# dcc.net
KiCad netlist of a schematic drawn in EAGLE
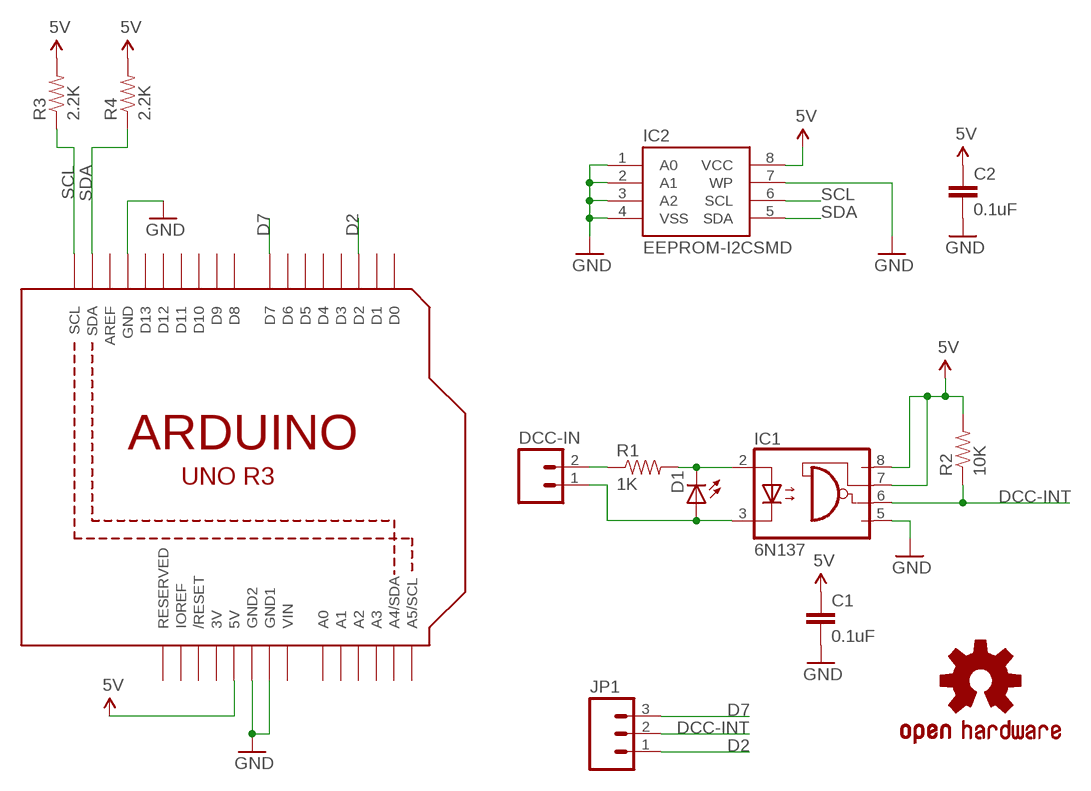
[diagram p0: schematic, sheet 1]

(export (version "E")
  (design (tool "Eeschema 10.0.6"))
  (components
    (comp (ref "C1")
      (value "0.1uF")
      (footprint "eagle-import:CAP-PTH-SMALL")
      (libsource (lib "eagle-import") (part "CAPPTH"))
    )
    (comp (ref "C2")
      (value "0.1uF")
      (footprint "eagle-import:0603-CAP")
      (libsource (lib "eagle-import") (part "0.1UF-25V(+80/-20%)(0603)"))
    )
    (comp (ref "D1")
      (value "LED5MM")
      (footprint "eagle-import:LED5MM")
      (libsource (lib "eagle-import") (part "LED5MM"))
    )
    (comp (ref "DCC-IN")
      (value "M025MM")
      (footprint "eagle-import:SCREWTERMINAL-5MM-2")
      (libsource (lib "eagle-import") (part "M025MM"))
    )
    (comp (ref "IC1")
      (value "6N137")
      (footprint "eagle-import:DIL08")
      (libsource (lib "eagle-import") (part "6N137"))
    )
    (comp (ref "IC2")
      (value "EEPROM-I2CSMD")
      (footprint "eagle-import:SO08")
      (libsource (lib "eagle-import") (part "EEPROM-I2CSMD"))
    )
    (comp (ref "JP1")
      (value "M03PTH")
      (footprint "eagle-import:1X03")
      (libsource (lib "eagle-import") (part "M03PTH"))
    )
    (comp (ref "LOGO1")
      (value "OSHW-LOGOL")
      (footprint "eagle-import:OSHW-LOGO-L")
      (libsource (lib "eagle-import") (part "OSHW-LOGOL"))
    )
    (comp (ref "R1")
      (value "1K")
      (footprint "eagle-import:AXIAL-0.4")
      (libsource (lib "eagle-import") (part "RESISTORPTH-1/4W"))
    )
    (comp (ref "R2")
      (value "10K")
      (footprint "eagle-import:AXIAL-0.4")
      (libsource (lib "eagle-import") (part "RESISTORPTH-1/4W"))
    )
    (comp (ref "R3")
      (value "2.2K")
      (footprint "eagle-import:0603-RES")
      (libsource (lib "eagle-import") (part "RESISTOR0603-RES"))
    )
    (comp (ref "R4")
      (value "2.2K")
      (footprint "eagle-import:0603-RES")
      (libsource (lib "eagle-import") (part "RESISTOR0603-RES"))
    )
    (comp (ref "U1")
      (value "ARDUINOR3-JUSTPINS")
      (footprint "eagle-import:ARDUINOR3")
      (libsource (lib "eagle-import") (part "ARDUINOR3-JUSTPINS"))
    )
  )
  (nets
    (net (code "1") (name "/3V") (class "Default")
      (node (ref "U1") (pin "3V") (pinfunction "3V_3V") (pintype "power_in"))
    )
    (net (code "2") (name "/D2") (class "Default")
      (node (ref "JP1") (pin "1") (pinfunction "1_1") (pintype "passive"))
      (node (ref "U1") (pin "D2") (pinfunction "D2_D2") (pintype "bidirectional"))
    )
    (net (code "3") (name "/D7") (class "Default")
      (node (ref "JP1") (pin "3") (pinfunction "3_3") (pintype "passive"))
      (node (ref "U1") (pin "D7") (pinfunction "D7_D7") (pintype "bidirectional"))
    )
    (net (code "4") (name "/DCC-INT") (class "Default")
      (node (ref "IC1") (pin "6") (pinfunction "VO_6") (pintype "passive"))
      (node (ref "JP1") (pin "2") (pinfunction "2_2") (pintype "passive"))
      (node (ref "R2") (pin "P$1") (pinfunction "1_P$1") (pintype "passive"))
    )
    (net (code "5") (name "/SCL") (class "Default")
      (node (ref "IC2") (pin "6") (pinfunction "SCL_6") (pintype "bidirectional"))
      (node (ref "R3") (pin "1") (pinfunction "1_1") (pintype "passive"))
      (node (ref "U1") (pin "SCL") (pinfunction "SCL_SCL") (pintype "bidirectional"))
    )
    (net (code "6") (name "/SDA") (class "Default")
      (node (ref "IC2") (pin "5") (pinfunction "SDA_5") (pintype "bidirectional"))
      (node (ref "R4") (pin "1") (pinfunction "1_1") (pintype "passive"))
      (node (ref "U1") (pin "SDA") (pinfunction "SDA_SDA") (pintype "bidirectional"))
    )
    (net (code "7") (name "/VIN") (class "Default")
      (node (ref "U1") (pin "VIN") (pinfunction "VIN_VIN") (pintype "power_in"))
    )
    (net (code "8") (name "5V") (class "Default")
      (node (ref "C1") (pin "1") (pinfunction "1_1") (pintype "passive"))
      (node (ref "C2") (pin "1") (pinfunction "1_1") (pintype "passive"))
      (node (ref "IC1") (pin "7") (pinfunction "VE_7") (pintype "passive"))
      (node (ref "IC1") (pin "8") (pinfunction "VCC_8") (pintype "passive"))
      (node (ref "IC2") (pin "8") (pinfunction "VCC_8") (pintype "power_in"))
      (node (ref "R2") (pin "P$2") (pinfunction "2_P$2") (pintype "passive"))
      (node (ref "R3") (pin "2") (pinfunction "2_2") (pintype "passive"))
      (node (ref "R4") (pin "2") (pinfunction "2_2") (pintype "passive"))
      (node (ref "U1") (pin "5V") (pinfunction "5V_5V") (pintype "power_in"))
    )
    (net (code "9") (name "GND") (class "Default")
      (node (ref "C1") (pin "2") (pinfunction "2_2") (pintype "passive"))
      (node (ref "C2") (pin "2") (pinfunction "2_2") (pintype "passive"))
      (node (ref "IC1") (pin "5") (pinfunction "GND_5") (pintype "passive"))
      (node (ref "IC2") (pin "1") (pinfunction "A0_1") (pintype "bidirectional"))
      (node (ref "IC2") (pin "2") (pinfunction "A1_2") (pintype "bidirectional"))
      (node (ref "IC2") (pin "3") (pinfunction "A2_3") (pintype "bidirectional"))
      (node (ref "IC2") (pin "4") (pinfunction "VSS_4") (pintype "power_in"))
      (node (ref "IC2") (pin "7") (pinfunction "WP_7") (pintype "bidirectional"))
      (node (ref "U1") (pin "GND") (pinfunction "GND_GND") (pintype "power_in"))
      (node (ref "U1") (pin "GND1") (pinfunction "GND1_GND1") (pintype "power_in"))
      (node (ref "U1") (pin "GND2") (pinfunction "GND2_GND2") (pintype "power_in"))
    )
    (net (code "10") (name "Net-(D1-C)") (class "Default")
      (node (ref "D1") (pin "K") (pinfunction "C_K") (pintype "passive"))
      (node (ref "IC1") (pin "2") (pinfunction "A_2") (pintype "passive"))
      (node (ref "R1") (pin "P$2") (pinfunction "2_P$2") (pintype "passive"))
    )
    (net (code "11") (name "Net-(IC1-C)") (class "Default")
      (node (ref "D1") (pin "A") (pinfunction "A_A") (pintype "passive"))
      (node (ref "DCC-IN") (pin "1") (pinfunction "1_1") (pintype "passive"))
      (node (ref "IC1") (pin "3") (pinfunction "C_3") (pintype "passive"))
    )
    (net (code "12") (name "Net-(R1-1)") (class "Default")
      (node (ref "DCC-IN") (pin "2") (pinfunction "2_2") (pintype "passive"))
      (node (ref "R1") (pin "P$1") (pinfunction "1_P$1") (pintype "passive"))
    )
    (net (code "13") (name "unconnected-(U1-A4{slash}SDA-PadA4)") (class "Default")
      (node (ref "U1") (pin "A4") (pinfunction "A4/SDA_A4") (pintype "bidirectional"))
    )
    (net (code "14") (name "unconnected-(U1-A5{slash}SCL-PadA5)") (class "Default")
      (node (ref "U1") (pin "A5") (pinfunction "A5/SCL_A5") (pintype "bidirectional"))
    )
    (net (code "15") (name "unconnected-(U1-PadA0)") (class "Default")
      (node (ref "U1") (pin "A0") (pinfunction "A0_A0") (pintype "bidirectional"))
    )
    (net (code "16") (name "unconnected-(U1-PadA1)") (class "Default")
      (node (ref "U1") (pin "A1") (pinfunction "A1_A1") (pintype "bidirectional"))
    )
    (net (code "17") (name "unconnected-(U1-PadA2)") (class "Default")
      (node (ref "U1") (pin "A2") (pinfunction "A2_A2") (pintype "bidirectional"))
    )
    (net (code "18") (name "unconnected-(U1-PadA3)") (class "Default")
      (node (ref "U1") (pin "A3") (pinfunction "A3_A3") (pintype "bidirectional"))
    )
    (net (code "19") (name "unconnected-(U1-PadAREF)") (class "Default")
      (node (ref "U1") (pin "AREF") (pinfunction "AREF_AREF") (pintype "bidirectional"))
    )
    (net (code "20") (name "unconnected-(U1-PadD0)") (class "Default")
      (node (ref "U1") (pin "D0") (pinfunction "D0_D0") (pintype "bidirectional"))
    )
    (net (code "21") (name "unconnected-(U1-PadD1)") (class "Default")
      (node (ref "U1") (pin "D1") (pinfunction "D1_D1") (pintype "bidirectional"))
    )
    (net (code "22") (name "unconnected-(U1-PadD3)") (class "Default")
      (node (ref "U1") (pin "D3") (pinfunction "D3_D3") (pintype "bidirectional"))
    )
    (net (code "23") (name "unconnected-(U1-PadD4)") (class "Default")
      (node (ref "U1") (pin "D4") (pinfunction "D4_D4") (pintype "bidirectional"))
    )
    (net (code "24") (name "unconnected-(U1-PadD5)") (class "Default")
      (node (ref "U1") (pin "D5") (pinfunction "D5_D5") (pintype "bidirectional"))
    )
    (net (code "25") (name "unconnected-(U1-PadD6)") (class "Default")
      (node (ref "U1") (pin "D6") (pinfunction "D6_D6") (pintype "bidirectional"))
    )
    (net (code "26") (name "unconnected-(U1-PadD8)") (class "Default")
      (node (ref "U1") (pin "D8") (pinfunction "D8_D8") (pintype "bidirectional"))
    )
    (net (code "27") (name "unconnected-(U1-PadD9)") (class "Default")
      (node (ref "U1") (pin "D9") (pinfunction "D9_D9") (pintype "bidirectional"))
    )
    (net (code "28") (name "unconnected-(U1-PadD10)") (class "Default")
      (node (ref "U1") (pin "D10") (pinfunction "D10_D10") (pintype "bidirectional"))
    )
    (net (code "29") (name "unconnected-(U1-PadD11)") (class "Default")
      (node (ref "U1") (pin "D11") (pinfunction "D11_D11") (pintype "bidirectional"))
    )
    (net (code "30") (name "unconnected-(U1-PadD12)") (class "Default")
      (node (ref "U1") (pin "D12") (pinfunction "D12_D12") (pintype "bidirectional"))
    )
    (net (code "31") (name "unconnected-(U1-PadD13)") (class "Default")
      (node (ref "U1") (pin "D13") (pinfunction "D13_D13") (pintype "bidirectional"))
    )
    (net (code "32") (name "unconnected-(U1-PadIOREF)") (class "Default")
      (node (ref "U1") (pin "IOREF") (pinfunction "IOREF_IOREF") (pintype "output"))
    )
    (net (code "33") (name "unconnected-(U1-PadRESERVED)") (class "Default")
      (node (ref "U1") (pin "RESERVED") (pinfunction "RESERVED_RESERVED") (pintype "no_connect"))
    )
    (net (code "34") (name "unconnected-(U1-{slash}RESET-PadRESET)") (class "Default")
      (node (ref "U1") (pin "RESET") (pinfunction "/RESET_RESET") (pintype "bidirectional"))
    )
  )
)
